# Photodiode.net
KiCad netlist of a schematic drawn in Altium Designer
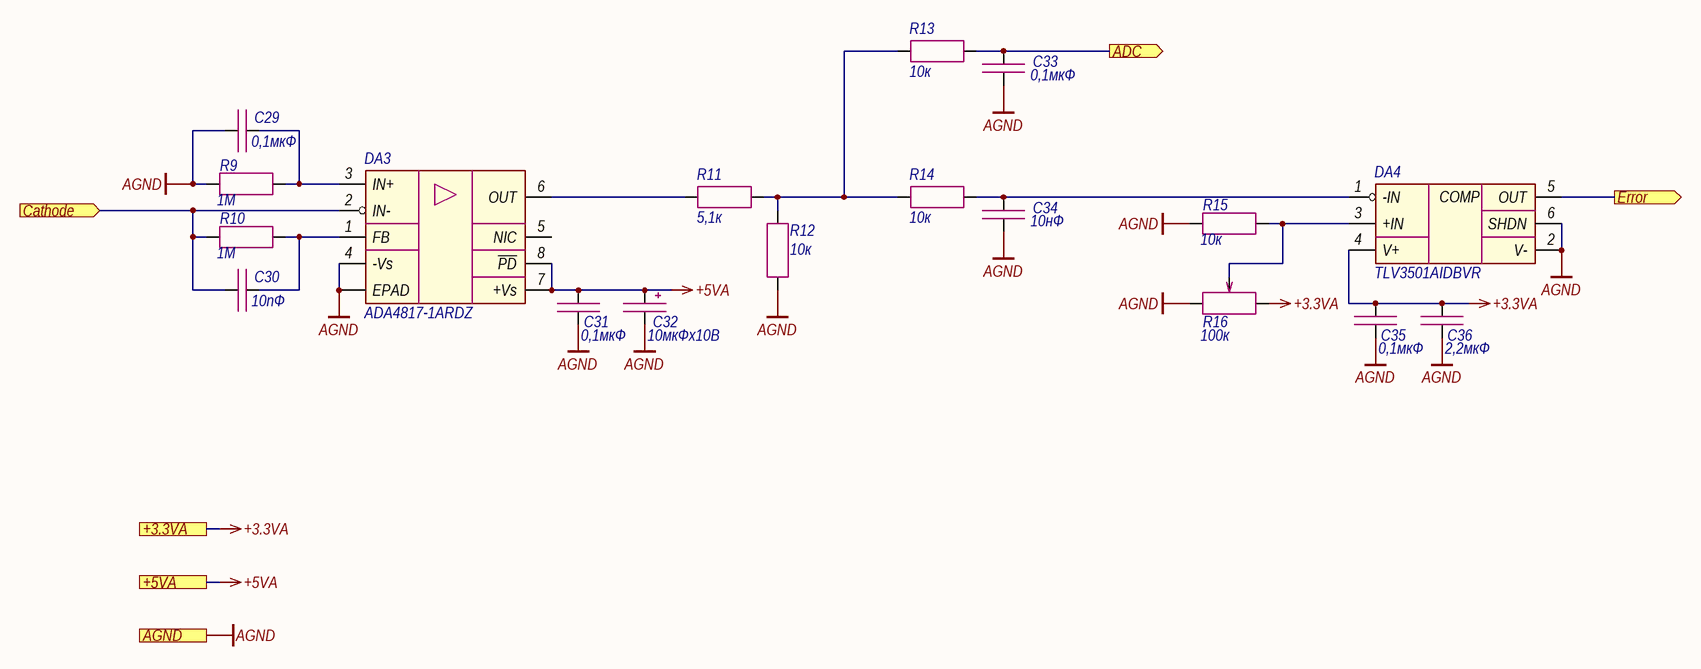
[diagram p0: Photodiode.SchDoc]

(export (version "E")
  (design (tool "Eeschema 10.0.6"))
  (components
    (comp (ref "C29")
      (value "0,1мкФ")
      (footprint "Pcb_library:CAP_0603")
      (fields (field (name "MANUFACTURER") "Murata"))
      (libsource (lib "Schem_library") (part "Capacitor"))
    )
    (comp (ref "C30")
      (value "10пФ")
      (footprint "Pcb_library:CAP_0603")
      (fields (field (name "MANUFACTURER") "Murata"))
      (libsource (lib "Schem_library") (part "Capacitor"))
    )
    (comp (ref "C31")
      (value "0,1мкФ")
      (footprint "Pcb_library:CAP_0603")
      (fields (field (name "MANUFACTURER") "Murata"))
      (libsource (lib "Schem_library") (part "Capacitor"))
    )
    (comp (ref "C32")
      (value "10мкФх10B")
      (footprint "Pcb_library:CAP_A")
      (libsource (lib "Schem_library") (part "Capacitor_Polar"))
    )
    (comp (ref "C33")
      (value "0,1мкФ")
      (footprint "Pcb_library:CAP_0603")
      (fields (field (name "MANUFACTURER") "Murata"))
      (libsource (lib "Schem_library") (part "Capacitor"))
    )
    (comp (ref "C34")
      (value "10нФ")
      (footprint "Pcb_library:CAP_0603")
      (fields (field (name "MANUFACTURER") "Murata"))
      (libsource (lib "Schem_library") (part "Capacitor"))
    )
    (comp (ref "C35")
      (value "0,1мкФ")
      (footprint "Pcb_library:CAP_0603")
      (fields (field (name "MANUFACTURER") "Murata"))
      (libsource (lib "Schem_library") (part "Capacitor"))
    )
    (comp (ref "C36")
      (value "2,2мкФ")
      (footprint "Pcb_library:CAP_0603")
      (fields (field (name "MANUFACTURER") "Murata"))
      (libsource (lib "Schem_library") (part "Capacitor"))
    )
    (comp (ref "DA3")
      (value "ADA4817-1ARDZ")
      (footprint "Pcb_library:SOIC-8 EPAD")
      (fields (field (name "MANUFACTURER") "Analog Devices"))
      (libsource (lib "Schem_library") (part "ADA4817-1ARDZ"))
    )
    (comp (ref "DA4")
      (value "TLV3501AIDBVR")
      (footprint "Pcb_library:SOT-23-6")
      (fields (field (name "MANUFACTURER") "Texas Instruments"))
      (libsource (lib "Schem_library") (part "TLV3501"))
    )
    (comp (ref "R9")
      (value "1М")
      (footprint "Pcb_library:RES_0805")
      (fields (field (name "MANUFACTURER") "Yageo"))
      (libsource (lib "Schem_library") (part "Resistor"))
    )
    (comp (ref "R10")
      (value "1М")
      (footprint "Pcb_library:RES_0805")
      (fields (field (name "MANUFACTURER") "Yageo"))
      (libsource (lib "Schem_library") (part "Resistor"))
    )
    (comp (ref "R11")
      (value "5,1к")
      (footprint "Pcb_library:RES_0603")
      (fields (field (name "MANUFACTURER") "Yageo"))
      (libsource (lib "Schem_library") (part "Resistor"))
    )
    (comp (ref "R12")
      (value "10к")
      (footprint "Pcb_library:RES_0603")
      (fields (field (name "MANUFACTURER") "Yageo"))
      (libsource (lib "Schem_library") (part "Resistor"))
    )
    (comp (ref "R13")
      (value "10к")
      (footprint "Pcb_library:RES_0603")
      (fields (field (name "MANUFACTURER") "Yageo"))
      (libsource (lib "Schem_library") (part "Resistor"))
    )
    (comp (ref "R14")
      (value "10к")
      (footprint "Pcb_library:RES_0603")
      (fields (field (name "MANUFACTURER") "Yageo"))
      (libsource (lib "Schem_library") (part "Resistor"))
    )
    (comp (ref "R15")
      (value "10к")
      (footprint "Pcb_library:RES_0603")
      (fields (field (name "MANUFACTURER") "Yageo"))
      (libsource (lib "Schem_library") (part "Resistor"))
    )
    (comp (ref "R16")
      (value "100к")
      (footprint "Pcb_library:3224W")
      (fields (field (name "MANUFACTURER") "Bourns"))
      (libsource (lib "Schem_library") (part "Resistor_Variable"))
    )
  )
  (nets
    (net (code "1") (name "+3.3VA") (class "Default")
      (node (ref "C35") (pin "1") (pinfunction "1_1") (pintype "passive"))
      (node (ref "C36") (pin "1") (pinfunction "1_1") (pintype "passive"))
      (node (ref "DA4") (pin "4") (pinfunction "V+_4") (pintype "passive"))
      (node (ref "R16") (pin "3") (pintype "passive"))
    )
    (net (code "2") (name "+5VA") (class "Default")
      (node (ref "C31") (pin "1") (pinfunction "1_1") (pintype "passive"))
      (node (ref "C32") (pin "1") (pinfunction "1_1") (pintype "passive"))
      (node (ref "DA3") (pin "7") (pinfunction "+Vs_7") (pintype "passive"))
      (node (ref "DA3") (pin "8") (pinfunction "~{PD}_8") (pintype "passive"))
    )
    (net (code "3") (name "/ADC") (class "Default")
      (node (ref "C33") (pin "1") (pinfunction "1_1") (pintype "passive"))
      (node (ref "R13") (pin "2") (pinfunction "2_2") (pintype "passive"))
    )
    (net (code "4") (name "/Cathode") (class "Default")
      (node (ref "C30") (pin "2") (pinfunction "2_2") (pintype "passive"))
      (node (ref "DA3") (pin "2") (pinfunction "IN-_2") (pintype "passive"))
      (node (ref "R10") (pin "2") (pinfunction "2_2") (pintype "passive"))
    )
    (net (code "5") (name "/Error") (class "Default")
      (node (ref "DA4") (pin "5") (pinfunction "OUT_5") (pintype "passive"))
    )
    (net (code "6") (name "AGND") (class "Default")
      (node (ref "C29") (pin "1") (pinfunction "1_1") (pintype "passive"))
      (node (ref "C31") (pin "2") (pinfunction "2_2") (pintype "passive"))
      (node (ref "C32") (pin "2") (pinfunction "2_2") (pintype "passive"))
      (node (ref "C33") (pin "2") (pinfunction "2_2") (pintype "passive"))
      (node (ref "C34") (pin "2") (pinfunction "2_2") (pintype "passive"))
      (node (ref "C35") (pin "2") (pinfunction "2_2") (pintype "passive"))
      (node (ref "C36") (pin "2") (pinfunction "2_2") (pintype "passive"))
      (node (ref "DA3") (pin "4") (pinfunction "-Vs_4") (pintype "passive"))
      (node (ref "DA3") (pin "EPAD") (pinfunction "EPAD_EPAD") (pintype "passive"))
      (node (ref "DA4") (pin "2") (pinfunction "V-_2") (pintype "passive"))
      (node (ref "DA4") (pin "6") (pinfunction "SHDN_6") (pintype "passive"))
      (node (ref "R12") (pin "2") (pinfunction "2_2") (pintype "passive"))
      (node (ref "R15") (pin "1") (pinfunction "1_1") (pintype "passive"))
      (node (ref "R16") (pin "1") (pintype "passive"))
      (node (ref "R9") (pin "2") (pinfunction "2_2") (pintype "passive"))
    )
    (net (code "7") (name "Net-(DA3-FB)") (class "Default")
      (node (ref "C30") (pin "1") (pinfunction "1_1") (pintype "passive"))
      (node (ref "DA3") (pin "1") (pinfunction "FB_1") (pintype "passive"))
      (node (ref "R10") (pin "1") (pinfunction "1_1") (pintype "passive"))
    )
    (net (code "8") (name "Net-(DA3-IN+)") (class "Default")
      (node (ref "C29") (pin "2") (pinfunction "2_2") (pintype "passive"))
      (node (ref "DA3") (pin "3") (pinfunction "IN+_3") (pintype "passive"))
      (node (ref "R9") (pin "1") (pinfunction "1_1") (pintype "passive"))
    )
    (net (code "9") (name "Net-(DA3-OUT)") (class "Default")
      (node (ref "DA3") (pin "6") (pinfunction "OUT_6") (pintype "passive"))
      (node (ref "R11") (pin "1") (pinfunction "1_1") (pintype "passive"))
    )
    (net (code "10") (name "Net-(DA4-+IN)") (class "Default")
      (node (ref "DA4") (pin "3") (pinfunction "+IN_3") (pintype "passive"))
      (node (ref "R15") (pin "2") (pinfunction "2_2") (pintype "passive"))
      (node (ref "R16") (pin "2") (pintype "passive"))
    )
    (net (code "11") (name "Net-(DA4--IN)") (class "Default")
      (node (ref "C34") (pin "1") (pinfunction "1_1") (pintype "passive"))
      (node (ref "DA4") (pin "1") (pinfunction "-IN_1") (pintype "passive"))
      (node (ref "R14") (pin "2") (pinfunction "2_2") (pintype "passive"))
    )
    (net (code "12") (name "Net-(R11-Pad2)") (class "Default")
      (node (ref "R11") (pin "2") (pinfunction "2_2") (pintype "passive"))
      (node (ref "R12") (pin "1") (pinfunction "1_1") (pintype "passive"))
      (node (ref "R13") (pin "1") (pinfunction "1_1") (pintype "passive"))
      (node (ref "R14") (pin "1") (pinfunction "1_1") (pintype "passive"))
    )
    (net (code "13") (name "unconnected-(DA3-NIC-Pad5)") (class "Default")
      (node (ref "DA3") (pin "5") (pinfunction "NIC_5") (pintype "passive"))
    )
  )
)
